# CLOCK_GENERATOR.net
KiCad netlist of a schematic drawn in Altium Designer
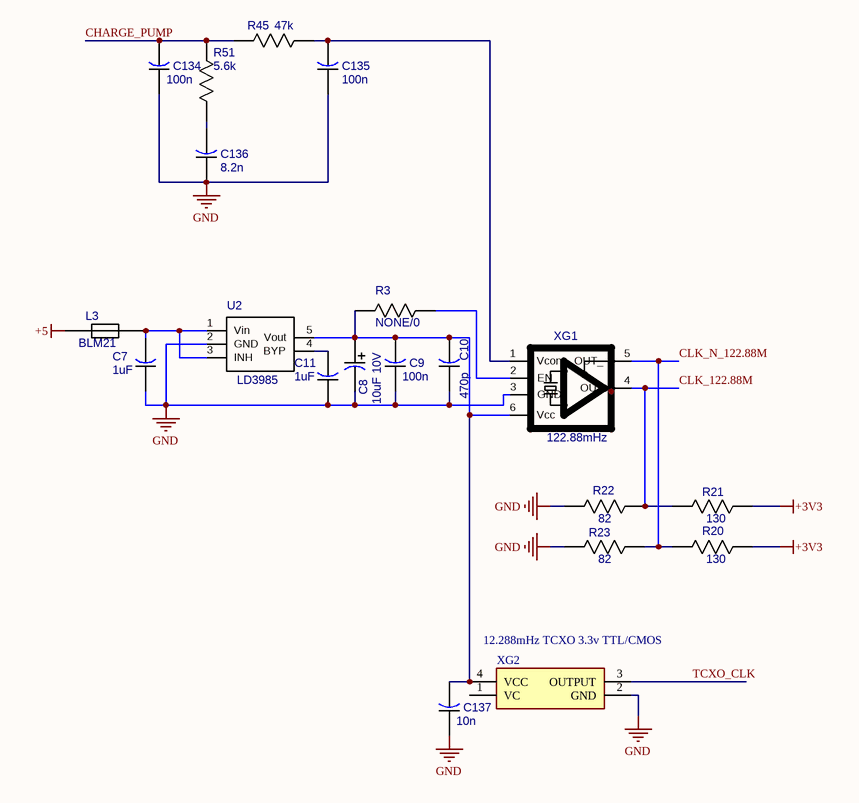
[diagram p0: CLOCK_GENERATOR.SchDoc]

(export (version "E")
  (design (tool "Eeschema 10.0.6"))
  (components
    (comp (ref "C7")
      (value "1uF")
      (footprint "CAP_0805")
      (description "CAP_0805")
      (libsource (lib "*") (part "CAP_0805"))
    )
    (comp (ref "C8")
      (value "10uF 10V")
      (footprint "CAPAE_4.3x4.3h5.4")
      (description "CAPAE_4.3x4.3h5.4")
      (libsource (lib "*") (part "CAPAE_4.3x4.3h5.4"))
    )
    (comp (ref "C9")
      (value "100n")
      (footprint "CAP_0805")
      (description "CAP_0805")
      (libsource (lib "*") (part "CAP_0805"))
    )
    (comp (ref "C10")
      (value "470p")
      (footprint "CAP_0805")
      (description "CAP_0805")
      (libsource (lib "*") (part "CAP_0805"))
    )
    (comp (ref "C11")
      (value "1uF")
      (footprint "CAP_0805")
      (description "CAP_0805")
      (libsource (lib "*") (part "CAP_0805"))
    )
    (comp (ref "C134")
      (value "100n")
      (footprint "CAP_0805")
      (description "CAP_0805")
      (libsource (lib "*") (part "CAP_0805"))
    )
    (comp (ref "C135")
      (value "100n")
      (footprint "CAP_0805")
      (description "CAP_0805")
      (libsource (lib "*") (part "CAP_0805"))
    )
    (comp (ref "C136")
      (value "8.2n")
      (footprint "CAP_0805")
      (description "CAP_0805")
      (libsource (lib "*") (part "CAP_0805"))
    )
    (comp (ref "C137")
      (value "10n")
      (footprint "CAP_0805")
      (description "CAP_0805")
      (libsource (lib "*") (part "CAP_0805"))
    )
    (comp (ref "L3")
      (value "BLM21")
      (footprint "CAP_0805")
      (libsource (lib "MOTHERBOARD_1") (part "IND_FERRITE_BEAD"))
    )
    (comp (ref "R3")
      (value "NONE/0")
      (footprint "RES_0805")
      (description "By used crystal")
      (fields (field (name "Comment") "0/NONE"))
      (libsource (lib "*") (part "RES_0805"))
    )
    (comp (ref "R20")
      (value "130")
      (footprint "RES_0805")
      (description "RES_0805")
      (libsource (lib "*") (part "RES_0805"))
    )
    (comp (ref "R21")
      (value "130")
      (footprint "RES_0805")
      (description "RES_0805")
      (libsource (lib "*") (part "RES_0805"))
    )
    (comp (ref "R22")
      (value "82")
      (footprint "RES_0805")
      (description "RES_0805")
      (libsource (lib "*") (part "RES_0805"))
    )
    (comp (ref "R23")
      (value "82")
      (footprint "RES_0805")
      (description "RES_0805")
      (libsource (lib "*") (part "RES_0805"))
    )
    (comp (ref "R45")
      (value "47k")
      (footprint "RES_0805")
      (description "RES_0805")
      (libsource (lib "*") (part "RES_0805"))
    )
    (comp (ref "R51")
      (value "5.6k")
      (footprint "RES_0805")
      (description "RES_0805")
      (libsource (lib "*") (part "RES_0805"))
    )
    (comp (ref "U2") (value "LD3985") (footprint "LD3985") (libsource (lib "*") (part "LD3985")))
    (comp (ref "XG1")
      (value "122.88mHz")
      (footprint "NV7050SA")
      (description "NV7050SA\r\nVG-4513CA-122.8800M-GGCT3")
      (libsource (lib "*") (part "NV7050SA"))
    )
    (comp (ref "XG2")
      (value "12.288mHz TCXO 3.3v TTL/CMOS")
      (footprint "SamacSys:581L200X2ITT")
      (description "Crystal or Oscillator")
      (fields
        (field (name "MANUFACTURER_PART_NUMBER") "581L200X2ITT")
        (field (name "MOUSER PART NUMBER") "774-581L200X2ITT")
      )
      (libsource (lib "*") (part "581L200X2ITT"))
    )
  )
  (nets
    (net (code "1") (name "+3V3") (class "Default")
      (node (ref "R20") (pin "1") (pinfunction "1_1") (pintype "passive"))
      (node (ref "R21") (pin "1") (pinfunction "1_1") (pintype "passive"))
    )
    (net (code "2") (name "+5") (class "Default")
      (node (ref "L3") (pin "1") (pinfunction "1_1") (pintype "passive"))
    )
    (net (code "3") (name "/CHARGE_PUMP") (class "Default")
      (node (ref "C134") (pin "2") (pinfunction "2_2") (pintype "passive"))
      (node (ref "R45") (pin "1") (pinfunction "1_1") (pintype "passive"))
      (node (ref "R51") (pin "1") (pinfunction "1_1") (pintype "passive"))
    )
    (net (code "4") (name "/CLK_122.88M") (class "Default")
      (node (ref "R21") (pin "2") (pinfunction "2_2") (pintype "passive"))
      (node (ref "R22") (pin "1") (pinfunction "1_1") (pintype "passive"))
      (node (ref "XG1") (pin "4") (pinfunction "OUT_4") (pintype "passive"))
    )
    (net (code "5") (name "/CLK_N_122.88M") (class "Default")
      (node (ref "R20") (pin "2") (pinfunction "2_2") (pintype "passive"))
      (node (ref "R23") (pin "1") (pinfunction "1_1") (pintype "passive"))
      (node (ref "XG1") (pin "5") (pinfunction "OUT__5") (pintype "passive"))
    )
    (net (code "6") (name "/TCXO_CLK") (class "Default")
      (node (ref "XG2") (pin "3") (pinfunction "OUTPUT_3") (pintype "passive"))
    )
    (net (code "7") (name "GND") (class "Default")
      (node (ref "C10") (pin "1") (pinfunction "1_1") (pintype "passive"))
      (node (ref "C11") (pin "1") (pinfunction "1_1") (pintype "passive"))
      (node (ref "C134") (pin "1") (pinfunction "1_1") (pintype "passive"))
      (node (ref "C135") (pin "1") (pinfunction "1_1") (pintype "passive"))
      (node (ref "C136") (pin "1") (pinfunction "1_1") (pintype "passive"))
      (node (ref "C137") (pin "1") (pinfunction "1_1") (pintype "passive"))
      (node (ref "C7") (pin "1") (pinfunction "1_1") (pintype "passive"))
      (node (ref "C8") (pin "2") (pinfunction "MINUS_2") (pintype "passive"))
      (node (ref "C9") (pin "1") (pinfunction "1_1") (pintype "passive"))
      (node (ref "R22") (pin "2") (pinfunction "2_2") (pintype "passive"))
      (node (ref "R23") (pin "2") (pinfunction "2_2") (pintype "passive"))
      (node (ref "U2") (pin "2") (pinfunction "GND_2") (pintype "passive"))
      (node (ref "XG1") (pin "3") (pinfunction "GND_3") (pintype "passive"))
      (node (ref "XG2") (pin "2") (pinfunction "GND_2") (pintype "passive"))
    )
    (net (code "8") (name "Net-(C8-PLUS)") (class "Default")
      (node (ref "C10") (pin "2") (pinfunction "2_2") (pintype "passive"))
      (node (ref "C137") (pin "2") (pinfunction "2_2") (pintype "passive"))
      (node (ref "C8") (pin "1") (pinfunction "PLUS_1") (pintype "passive"))
      (node (ref "C9") (pin "2") (pinfunction "2_2") (pintype "passive"))
      (node (ref "R3") (pin "1") (pinfunction "1_1") (pintype "passive"))
      (node (ref "U2") (pin "5") (pinfunction "Vout_5") (pintype "passive"))
      (node (ref "XG1") (pin "6") (pinfunction "Vcc_6") (pintype "passive"))
      (node (ref "XG2") (pin "4") (pinfunction "VCC_4") (pintype "passive"))
    )
    (net (code "9") (name "Net-(C136-Pad2)") (class "Default")
      (node (ref "C136") (pin "2") (pinfunction "2_2") (pintype "passive"))
      (node (ref "R51") (pin "2") (pinfunction "2_2") (pintype "passive"))
    )
    (net (code "10") (name "Net-(U2-BYP)") (class "Default")
      (node (ref "C11") (pin "2") (pinfunction "2_2") (pintype "passive"))
      (node (ref "U2") (pin "4") (pinfunction "BYP_4") (pintype "passive"))
    )
    (net (code "11") (name "Net-(U2-INH)") (class "Default")
      (node (ref "C7") (pin "2") (pinfunction "2_2") (pintype "passive"))
      (node (ref "L3") (pin "2") (pinfunction "2_2") (pintype "passive"))
      (node (ref "U2") (pin "1") (pinfunction "Vin_1") (pintype "passive"))
      (node (ref "U2") (pin "3") (pinfunction "INH_3") (pintype "passive"))
    )
    (net (code "12") (name "Net-(XG1-EN)") (class "Default")
      (node (ref "R3") (pin "2") (pinfunction "2_2") (pintype "passive"))
      (node (ref "XG1") (pin "2") (pinfunction "EN_2") (pintype "passive"))
    )
    (net (code "13") (name "Net-(XG1-Vcont)") (class "Default")
      (node (ref "C135") (pin "2") (pinfunction "2_2") (pintype "passive"))
      (node (ref "R45") (pin "2") (pinfunction "2_2") (pintype "passive"))
      (node (ref "XG1") (pin "1") (pinfunction "Vcont_1") (pintype "passive"))
    )
    (net (code "14") (name "unconnected-(XG2-VC-Pad1)") (class "Default")
      (node (ref "XG2") (pin "1") (pinfunction "VC_1") (pintype "passive"))
    )
  )
)
